# PWM_BoardSchem.net
KiCad netlist of a schematic drawn in Altium Designer
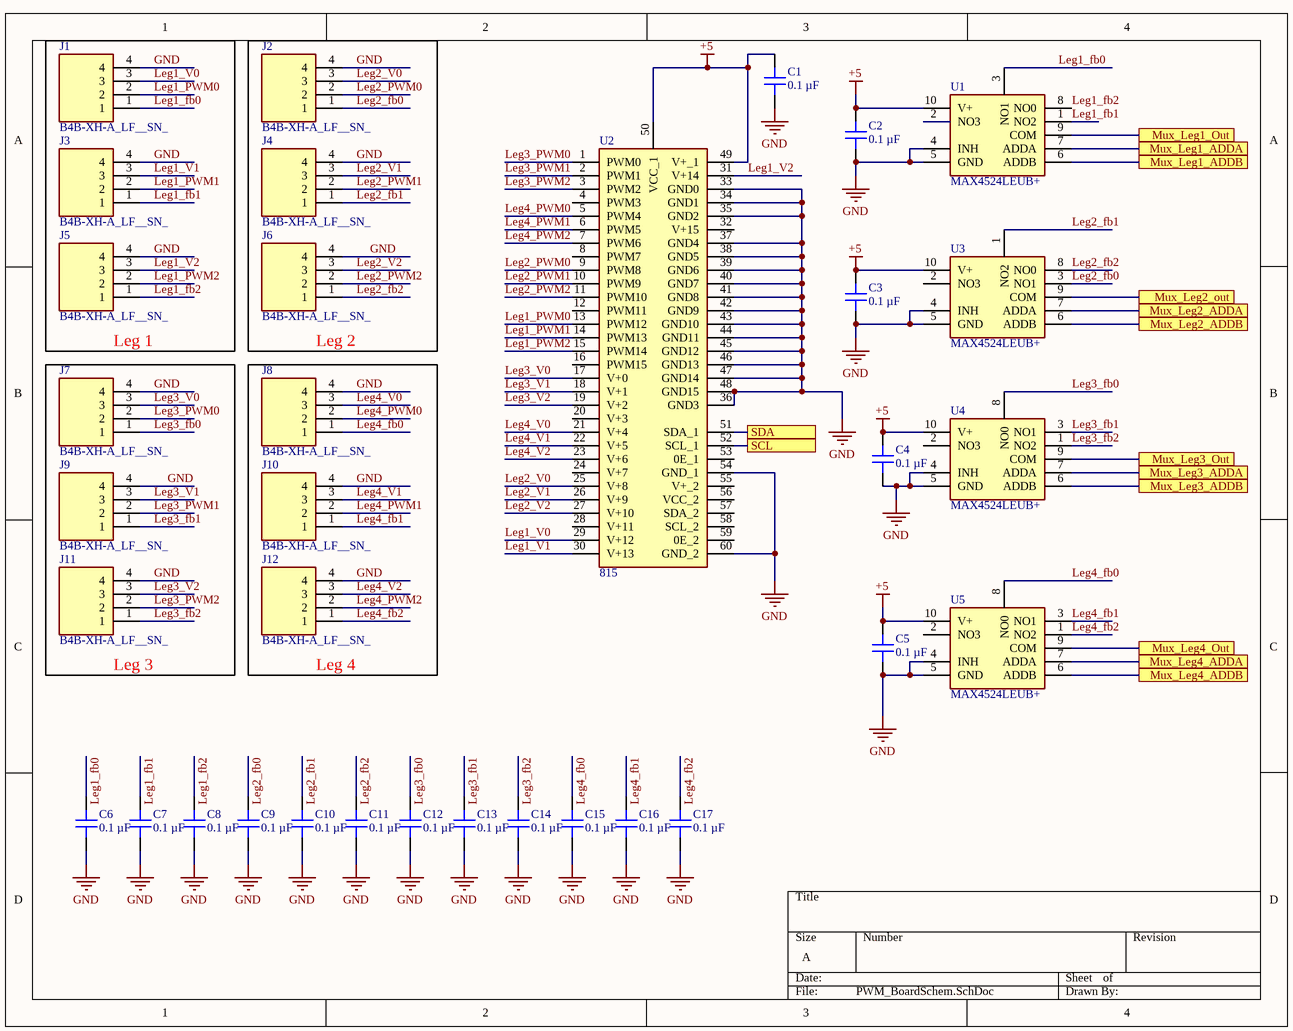
[diagram p0: PWM_BoardSchem.SchDoc]

(export (version "E")
  (design (tool "Eeschema 10.0.6"))
  (components
    (comp (ref "C1")
      (value "0.1 µF")
      (footprint "CAP 1210_3225 - 1MM")
      (description "CAP CER 0.1UF 50V C0G/NP0 1210")
      (fields (field (name "PART NUMBER") "C1210C104J5GACAUTO") (field (name "MANUFACTURER") "KEMET"))
      (libsource (lib "Celestial Altium Library - altium_library") (part "Capacitor"))
    )
    (comp (ref "C2")
      (value "0.1 µF")
      (footprint "CAP 1210_3225 - 1MM")
      (description "CAP CER 0.1UF 50V C0G/NP0 1210")
      (fields (field (name "PART NUMBER") "C1210C104J5GACAUTO") (field (name "MANUFACTURER") "KEMET"))
      (libsource (lib "Celestial Altium Library - altium_library") (part "Capacitor"))
    )
    (comp (ref "C3")
      (value "0.1 µF")
      (footprint "CAP 1210_3225 - 1MM")
      (description "CAP CER 0.1UF 50V C0G/NP0 1210")
      (fields (field (name "PART NUMBER") "C1210C104J5GACAUTO") (field (name "MANUFACTURER") "KEMET"))
      (libsource (lib "Celestial Altium Library - altium_library") (part "Capacitor"))
    )
    (comp (ref "C4")
      (value "0.1 µF")
      (footprint "CAP 1210_3225 - 1MM")
      (description "CAP CER 0.1UF 50V C0G/NP0 1210")
      (fields (field (name "PART NUMBER") "C1210C104J5GACAUTO") (field (name "MANUFACTURER") "KEMET"))
      (libsource (lib "Celestial Altium Library - altium_library") (part "Capacitor"))
    )
    (comp (ref "C5")
      (value "0.1 µF")
      (footprint "CAP 1210_3225 - 1MM")
      (description "CAP CER 0.1UF 50V C0G/NP0 1210")
      (fields (field (name "PART NUMBER") "C1210C104J5GACAUTO") (field (name "MANUFACTURER") "KEMET"))
      (libsource (lib "Celestial Altium Library - altium_library") (part "Capacitor"))
    )
    (comp (ref "C6")
      (value "0.1 µF")
      (footprint "CAP 1210_3225 - 1MM")
      (description "CAP CER 0.1UF 50V C0G/NP0 1210")
      (fields (field (name "PART NUMBER") "C1210C104J5GACAUTO") (field (name "MANUFACTURER") "KEMET"))
      (libsource (lib "Celestial Altium Library - altium_library") (part "Capacitor"))
    )
    (comp (ref "C7")
      (value "0.1 µF")
      (footprint "CAP 1210_3225 - 1MM")
      (description "CAP CER 0.1UF 50V C0G/NP0 1210")
      (fields (field (name "PART NUMBER") "C1210C104J5GACAUTO") (field (name "MANUFACTURER") "KEMET"))
      (libsource (lib "Celestial Altium Library - altium_library") (part "Capacitor"))
    )
    (comp (ref "C8")
      (value "0.1 µF")
      (footprint "CAP 1210_3225 - 1MM")
      (description "CAP CER 0.1UF 50V C0G/NP0 1210")
      (fields (field (name "PART NUMBER") "C1210C104J5GACAUTO") (field (name "MANUFACTURER") "KEMET"))
      (libsource (lib "Celestial Altium Library - altium_library") (part "Capacitor"))
    )
    (comp (ref "C9")
      (value "0.1 µF")
      (footprint "CAP 1210_3225 - 1MM")
      (description "CAP CER 0.1UF 50V C0G/NP0 1210")
      (fields (field (name "PART NUMBER") "C1210C104J5GACAUTO") (field (name "MANUFACTURER") "KEMET"))
      (libsource (lib "Celestial Altium Library - altium_library") (part "Capacitor"))
    )
    (comp (ref "C10")
      (value "0.1 µF")
      (footprint "CAP 1210_3225 - 1MM")
      (description "CAP CER 0.1UF 50V C0G/NP0 1210")
      (fields (field (name "PART NUMBER") "C1210C104J5GACAUTO") (field (name "MANUFACTURER") "KEMET"))
      (libsource (lib "Celestial Altium Library - altium_library") (part "Capacitor"))
    )
    (comp (ref "C11")
      (value "0.1 µF")
      (footprint "CAP 1210_3225 - 1MM")
      (description "CAP CER 0.1UF 50V C0G/NP0 1210")
      (fields (field (name "PART NUMBER") "C1210C104J5GACAUTO") (field (name "MANUFACTURER") "KEMET"))
      (libsource (lib "Celestial Altium Library - altium_library") (part "Capacitor"))
    )
    (comp (ref "C12")
      (value "0.1 µF")
      (footprint "CAP 1210_3225 - 1MM")
      (description "CAP CER 0.1UF 50V C0G/NP0 1210")
      (fields (field (name "PART NUMBER") "C1210C104J5GACAUTO") (field (name "MANUFACTURER") "KEMET"))
      (libsource (lib "Celestial Altium Library - altium_library") (part "Capacitor"))
    )
    (comp (ref "C13")
      (value "0.1 µF")
      (footprint "CAP 1210_3225 - 1MM")
      (description "CAP CER 0.1UF 50V C0G/NP0 1210")
      (fields (field (name "PART NUMBER") "C1210C104J5GACAUTO") (field (name "MANUFACTURER") "KEMET"))
      (libsource (lib "Celestial Altium Library - altium_library") (part "Capacitor"))
    )
    (comp (ref "C14")
      (value "0.1 µF")
      (footprint "CAP 1210_3225 - 1MM")
      (description "CAP CER 0.1UF 50V C0G/NP0 1210")
      (fields (field (name "PART NUMBER") "C1210C104J5GACAUTO") (field (name "MANUFACTURER") "KEMET"))
      (libsource (lib "Celestial Altium Library - altium_library") (part "Capacitor"))
    )
    (comp (ref "C15")
      (value "0.1 µF")
      (footprint "CAP 1210_3225 - 1MM")
      (description "CAP CER 0.1UF 50V C0G/NP0 1210")
      (fields (field (name "PART NUMBER") "C1210C104J5GACAUTO") (field (name "MANUFACTURER") "KEMET"))
      (libsource (lib "Celestial Altium Library - altium_library") (part "Capacitor"))
    )
    (comp (ref "C16")
      (value "0.1 µF")
      (footprint "CAP 1210_3225 - 1MM")
      (description "CAP CER 0.1UF 50V C0G/NP0 1210")
      (fields (field (name "PART NUMBER") "C1210C104J5GACAUTO") (field (name "MANUFACTURER") "KEMET"))
      (libsource (lib "Celestial Altium Library - altium_library") (part "Capacitor"))
    )
    (comp (ref "C17")
      (value "0.1 µF")
      (footprint "CAP 1210_3225 - 1MM")
      (description "CAP CER 0.1UF 50V C0G/NP0 1210")
      (fields (field (name "PART NUMBER") "C1210C104J5GACAUTO") (field (name "MANUFACTURER") "KEMET"))
      (libsource (lib "Celestial Altium Library - altium_library") (part "Capacitor"))
    )
    (comp (ref "J1")
      (value "B4B-XH-A_LF__SN_")
      (footprint "SamacSys:B4BXHALFSN")
      (description "Connector")
      (fields (field (name "MANUFACTURER_PART_NUMBER") "B4B-XH-A(LF)(SN)"))
      (libsource (lib "*") (part "B4B-XH-A_LF__SN_"))
    )
    (comp (ref "J2")
      (value "B4B-XH-A_LF__SN_")
      (footprint "SamacSys:B4BXHALFSN")
      (description "Connector")
      (fields (field (name "MANUFACTURER_PART_NUMBER") "B4B-XH-A(LF)(SN)"))
      (libsource (lib "*") (part "B4B-XH-A_LF__SN_"))
    )
    (comp (ref "J3")
      (value "B4B-XH-A_LF__SN_")
      (footprint "SamacSys:B4BXHALFSN")
      (description "Connector")
      (fields (field (name "MANUFACTURER_PART_NUMBER") "B4B-XH-A(LF)(SN)"))
      (libsource (lib "*") (part "B4B-XH-A_LF__SN_"))
    )
    (comp (ref "J4")
      (value "B4B-XH-A_LF__SN_")
      (footprint "SamacSys:B4BXHALFSN")
      (description "Connector")
      (fields (field (name "MANUFACTURER_PART_NUMBER") "B4B-XH-A(LF)(SN)"))
      (libsource (lib "*") (part "B4B-XH-A_LF__SN_"))
    )
    (comp (ref "J5")
      (value "B4B-XH-A_LF__SN_")
      (footprint "SamacSys:B4BXHALFSN")
      (description "Connector")
      (fields (field (name "MANUFACTURER_PART_NUMBER") "B4B-XH-A(LF)(SN)"))
      (libsource (lib "*") (part "B4B-XH-A_LF__SN_"))
    )
    (comp (ref "J6")
      (value "B4B-XH-A_LF__SN_")
      (footprint "SamacSys:B4BXHALFSN")
      (description "Connector")
      (fields (field (name "MANUFACTURER_PART_NUMBER") "B4B-XH-A(LF)(SN)"))
      (libsource (lib "*") (part "B4B-XH-A_LF__SN_"))
    )
    (comp (ref "J7")
      (value "B4B-XH-A_LF__SN_")
      (footprint "SamacSys:B4BXHALFSN")
      (description "Connector")
      (fields (field (name "MANUFACTURER_PART_NUMBER") "B4B-XH-A(LF)(SN)"))
      (libsource (lib "*") (part "B4B-XH-A_LF__SN_"))
    )
    (comp (ref "J8")
      (value "B4B-XH-A_LF__SN_")
      (footprint "SamacSys:B4BXHALFSN")
      (description "Connector")
      (fields (field (name "MANUFACTURER_PART_NUMBER") "B4B-XH-A(LF)(SN)"))
      (libsource (lib "*") (part "B4B-XH-A_LF__SN_"))
    )
    (comp (ref "J9")
      (value "B4B-XH-A_LF__SN_")
      (footprint "SamacSys:B4BXHALFSN")
      (description "Connector")
      (fields (field (name "MANUFACTURER_PART_NUMBER") "B4B-XH-A(LF)(SN)"))
      (libsource (lib "*") (part "B4B-XH-A_LF__SN_"))
    )
    (comp (ref "J10")
      (value "B4B-XH-A_LF__SN_")
      (footprint "SamacSys:B4BXHALFSN")
      (description "Connector")
      (fields (field (name "MANUFACTURER_PART_NUMBER") "B4B-XH-A(LF)(SN)"))
      (libsource (lib "*") (part "B4B-XH-A_LF__SN_"))
    )
    (comp (ref "J11")
      (value "B4B-XH-A_LF__SN_")
      (footprint "SamacSys:B4BXHALFSN")
      (description "Connector")
      (fields (field (name "MANUFACTURER_PART_NUMBER") "B4B-XH-A(LF)(SN)"))
      (libsource (lib "*") (part "B4B-XH-A_LF__SN_"))
    )
    (comp (ref "J12")
      (value "B4B-XH-A_LF__SN_")
      (footprint "SamacSys:B4BXHALFSN")
      (description "Connector")
      (fields (field (name "MANUFACTURER_PART_NUMBER") "B4B-XH-A(LF)(SN)"))
      (libsource (lib "*") (part "B4B-XH-A_LF__SN_"))
    )
    (comp (ref "U1")
      (value "MAX4524LEUB+")
      (footprint "SamacSys:SOP50P490X110-10N")
      (description "Integrated Circuit")
      (fields (field (name "MOUSER PART NUMBER") "700-MAX4524LEUB+"))
      (libsource (lib "") (part "MAX4524LEUB+_1"))
    )
    (comp (ref "U2")
      (value "815")
      (footprint "SamacSys:815")
      (description "Undefined or Miscellaneous")
      (fields (field (name "MOUSER PART NUMBER") "485-815"))
      (libsource (lib "*") (part "815"))
    )
    (comp (ref "U3")
      (value "MAX4524LEUB+")
      (footprint "SamacSys:SOP50P490X110-10N")
      (description "Integrated Circuit")
      (fields (field (name "MOUSER PART NUMBER") "700-MAX4524LEUB+"))
      (libsource (lib "") (part "MAX4524LEUB+_2"))
    )
    (comp (ref "U4")
      (value "MAX4524LEUB+")
      (footprint "SamacSys:SOP50P490X110-10N")
      (description "Integrated Circuit")
      (fields (field (name "MOUSER PART NUMBER") "700-MAX4524LEUB+"))
      (libsource (lib "*") (part "MAX4524LEUB+"))
    )
    (comp (ref "U5")
      (value "MAX4524LEUB+")
      (footprint "SamacSys:SOP50P490X110-10N")
      (description "Integrated Circuit")
      (fields (field (name "MOUSER PART NUMBER") "700-MAX4524LEUB+"))
      (libsource (lib "*") (part "MAX4524LEUB+"))
    )
  )
  (nets
    (net (code "1") (name "+5") (class "Default")
      (node (ref "C1") (pin "2") (pinfunction "2_2") (pintype "passive"))
      (node (ref "C2") (pin "2") (pinfunction "2_2") (pintype "passive"))
      (node (ref "C3") (pin "2") (pinfunction "2_2") (pintype "passive"))
      (node (ref "C4") (pin "2") (pinfunction "2_2") (pintype "passive"))
      (node (ref "C5") (pin "2") (pinfunction "2_2") (pintype "passive"))
      (node (ref "U1") (pin "10") (pinfunction "V+_10") (pintype "passive"))
      (node (ref "U2") (pin "49") (pinfunction "V+_1_49") (pintype "passive"))
      (node (ref "U2") (pin "50") (pinfunction "VCC_1_50") (pintype "passive"))
      (node (ref "U3") (pin "10") (pinfunction "V+_10") (pintype "passive"))
      (node (ref "U4") (pin "10") (pinfunction "V+_10") (pintype "passive"))
      (node (ref "U5") (pin "10") (pinfunction "V+_10") (pintype "passive"))
    )
    (net (code "3") (name "/Leg1_PWM0") (class "Default")
      (node (ref "J1") (pin "2") (pinfunction "2_2") (pintype "passive"))
      (node (ref "U2") (pin "13") (pinfunction "PWM12_13") (pintype "passive"))
    )
    (net (code "4") (name "/Leg1_PWM1") (class "Default")
      (node (ref "J3") (pin "2") (pinfunction "2_2") (pintype "passive"))
      (node (ref "U2") (pin "14") (pinfunction "PWM13_14") (pintype "passive"))
    )
    (net (code "5") (name "/Leg1_PWM2") (class "Default")
      (node (ref "J5") (pin "2") (pinfunction "2_2") (pintype "passive"))
      (node (ref "U2") (pin "15") (pinfunction "PWM14_15") (pintype "passive"))
    )
    (net (code "6") (name "/Leg1_V0") (class "Default")
      (node (ref "J1") (pin "3") (pinfunction "3_3") (pintype "passive"))
      (node (ref "U2") (pin "29") (pinfunction "V+12_29") (pintype "passive"))
    )
    (net (code "7") (name "/Leg1_V1") (class "Default")
      (node (ref "J3") (pin "3") (pinfunction "3_3") (pintype "passive"))
      (node (ref "U2") (pin "30") (pinfunction "V+13_30") (pintype "passive"))
    )
    (net (code "8") (name "/Leg1_V2") (class "Default")
      (node (ref "J5") (pin "3") (pinfunction "3_3") (pintype "passive"))
      (node (ref "U2") (pin "31") (pinfunction "V+14_31") (pintype "passive"))
    )
    (net (code "9") (name "/Leg1_fb0") (class "Default")
      (node (ref "C6") (pin "2") (pinfunction "2_2") (pintype "passive"))
      (node (ref "J1") (pin "1") (pinfunction "1_1") (pintype "passive"))
      (node (ref "U1") (pin "3") (pinfunction "NO1_3") (pintype "passive"))
    )
    (net (code "10") (name "/Leg1_fb1") (class "Default")
      (node (ref "C7") (pin "2") (pinfunction "2_2") (pintype "passive"))
      (node (ref "J3") (pin "1") (pinfunction "1_1") (pintype "passive"))
      (node (ref "U1") (pin "1") (pinfunction "NO2_1") (pintype "passive"))
    )
    (net (code "11") (name "/Leg1_fb2") (class "Default")
      (node (ref "C8") (pin "2") (pinfunction "2_2") (pintype "passive"))
      (node (ref "J5") (pin "1") (pinfunction "1_1") (pintype "passive"))
      (node (ref "U1") (pin "8") (pinfunction "NO0_8") (pintype "passive"))
    )
    (net (code "12") (name "/Leg2_PWM0") (class "Default")
      (node (ref "J2") (pin "2") (pinfunction "2_2") (pintype "passive"))
      (node (ref "U2") (pin "9") (pinfunction "PWM8_9") (pintype "passive"))
    )
    (net (code "13") (name "/Leg2_PWM1") (class "Default")
      (node (ref "J4") (pin "2") (pinfunction "2_2") (pintype "passive"))
      (node (ref "U2") (pin "10") (pinfunction "PWM9_10") (pintype "passive"))
    )
    (net (code "14") (name "/Leg2_PWM2") (class "Default")
      (node (ref "J6") (pin "2") (pinfunction "2_2") (pintype "passive"))
      (node (ref "U2") (pin "11") (pinfunction "PWM10_11") (pintype "passive"))
    )
    (net (code "15") (name "/Leg2_V0") (class "Default")
      (node (ref "J2") (pin "3") (pinfunction "3_3") (pintype "passive"))
      (node (ref "U2") (pin "25") (pinfunction "V+8_25") (pintype "passive"))
    )
    (net (code "16") (name "/Leg2_V1") (class "Default")
      (node (ref "J4") (pin "3") (pinfunction "3_3") (pintype "passive"))
      (node (ref "U2") (pin "26") (pinfunction "V+9_26") (pintype "passive"))
    )
    (net (code "17") (name "/Leg2_V2") (class "Default")
      (node (ref "J6") (pin "3") (pinfunction "3_3") (pintype "passive"))
      (node (ref "U2") (pin "27") (pinfunction "V+10_27") (pintype "passive"))
    )
    (net (code "18") (name "/Leg2_fb0") (class "Default")
      (node (ref "C9") (pin "2") (pinfunction "2_2") (pintype "passive"))
      (node (ref "J2") (pin "1") (pinfunction "1_1") (pintype "passive"))
      (node (ref "U3") (pin "3") (pinfunction "NO1_3") (pintype "passive"))
    )
    (net (code "19") (name "/Leg2_fb1") (class "Default")
      (node (ref "C10") (pin "2") (pinfunction "2_2") (pintype "passive"))
      (node (ref "J4") (pin "1") (pinfunction "1_1") (pintype "passive"))
      (node (ref "U3") (pin "1") (pinfunction "NO2_1") (pintype "passive"))
    )
    (net (code "20") (name "/Leg2_fb2") (class "Default")
      (node (ref "C11") (pin "2") (pinfunction "2_2") (pintype "passive"))
      (node (ref "J6") (pin "1") (pinfunction "1_1") (pintype "passive"))
      (node (ref "U3") (pin "8") (pinfunction "NO0_8") (pintype "passive"))
    )
    (net (code "21") (name "/Leg3_PWM0") (class "Default")
      (node (ref "J7") (pin "2") (pinfunction "2_2") (pintype "passive"))
      (node (ref "U2") (pin "1") (pinfunction "PWM0_1") (pintype "passive"))
    )
    (net (code "22") (name "/Leg3_PWM1") (class "Default")
      (node (ref "J9") (pin "2") (pinfunction "2_2") (pintype "passive"))
      (node (ref "U2") (pin "2") (pinfunction "PWM1_2") (pintype "passive"))
    )
    (net (code "23") (name "/Leg3_PWM2") (class "Default")
      (node (ref "J11") (pin "2") (pinfunction "2_2") (pintype "passive"))
      (node (ref "U2") (pin "3") (pinfunction "PWM2_3") (pintype "passive"))
    )
    (net (code "24") (name "/Leg3_V0") (class "Default")
      (node (ref "J7") (pin "3") (pinfunction "3_3") (pintype "passive"))
      (node (ref "U2") (pin "17") (pinfunction "V+0_17") (pintype "passive"))
    )
    (net (code "25") (name "/Leg3_V1") (class "Default")
      (node (ref "J9") (pin "3") (pinfunction "3_3") (pintype "passive"))
      (node (ref "U2") (pin "18") (pinfunction "V+1_18") (pintype "passive"))
    )
    (net (code "26") (name "/Leg3_V2") (class "Default")
      (node (ref "J11") (pin "3") (pinfunction "3_3") (pintype "passive"))
      (node (ref "U2") (pin "19") (pinfunction "V+2_19") (pintype "passive"))
    )
    (net (code "27") (name "/Leg3_fb0") (class "Default")
      (node (ref "C12") (pin "2") (pinfunction "2_2") (pintype "passive"))
      (node (ref "J7") (pin "1") (pinfunction "1_1") (pintype "passive"))
      (node (ref "U4") (pin "8") (pinfunction "NO0_8") (pintype "passive"))
    )
    (net (code "28") (name "/Leg3_fb1") (class "Default")
      (node (ref "C13") (pin "2") (pinfunction "2_2") (pintype "passive"))
      (node (ref "J9") (pin "1") (pinfunction "1_1") (pintype "passive"))
      (node (ref "U4") (pin "3") (pinfunction "NO1_3") (pintype "passive"))
    )
    (net (code "29") (name "/Leg3_fb2") (class "Default")
      (node (ref "C14") (pin "2") (pinfunction "2_2") (pintype "passive"))
      (node (ref "J11") (pin "1") (pinfunction "1_1") (pintype "passive"))
      (node (ref "U4") (pin "1") (pinfunction "NO2_1") (pintype "passive"))
    )
    (net (code "30") (name "/Leg4_PWM0") (class "Default")
      (node (ref "J8") (pin "2") (pinfunction "2_2") (pintype "passive"))
      (node (ref "U2") (pin "5") (pinfunction "PWM4_5") (pintype "passive"))
    )
    (net (code "31") (name "/Leg4_PWM1") (class "Default")
      (node (ref "J10") (pin "2") (pinfunction "2_2") (pintype "passive"))
      (node (ref "U2") (pin "6") (pinfunction "PWM5_6") (pintype "passive"))
    )
    (net (code "32") (name "/Leg4_PWM2") (class "Default")
      (node (ref "J12") (pin "2") (pinfunction "2_2") (pintype "passive"))
      (node (ref "U2") (pin "7") (pinfunction "PWM6_7") (pintype "passive"))
    )
    (net (code "33") (name "/Leg4_V0") (class "Default")
      (node (ref "J8") (pin "3") (pinfunction "3_3") (pintype "passive"))
      (node (ref "U2") (pin "21") (pinfunction "V+4_21") (pintype "passive"))
    )
    (net (code "34") (name "/Leg4_V1") (class "Default")
      (node (ref "J10") (pin "3") (pinfunction "3_3") (pintype "passive"))
      (node (ref "U2") (pin "22") (pinfunction "V+5_22") (pintype "passive"))
    )
    (net (code "35") (name "/Leg4_V2") (class "Default")
      (node (ref "J12") (pin "3") (pinfunction "3_3") (pintype "passive"))
      (node (ref "U2") (pin "23") (pinfunction "V+6_23") (pintype "passive"))
    )
    (net (code "36") (name "/Leg4_fb0") (class "Default")
      (node (ref "C15") (pin "2") (pinfunction "2_2") (pintype "passive"))
      (node (ref "J8") (pin "1") (pinfunction "1_1") (pintype "passive"))
      (node (ref "U5") (pin "8") (pinfunction "NO0_8") (pintype "passive"))
    )
    (net (code "37") (name "/Leg4_fb1") (class "Default")
      (node (ref "C16") (pin "2") (pinfunction "2_2") (pintype "passive"))
      (node (ref "J10") (pin "1") (pinfunction "1_1") (pintype "passive"))
      (node (ref "U5") (pin "3") (pinfunction "NO1_3") (pintype "passive"))
    )
    (net (code "38") (name "/Leg4_fb2") (class "Default")
      (node (ref "C17") (pin "2") (pinfunction "2_2") (pintype "passive"))
      (node (ref "J12") (pin "1") (pinfunction "1_1") (pintype "passive"))
      (node (ref "U5") (pin "1") (pinfunction "NO2_1") (pintype "passive"))
    )
    (net (code "39") (name "/Mux_Leg1_ADDA") (class "Default")
      (node (ref "U1") (pin "7") (pinfunction "ADDA_7") (pintype "passive"))
    )
    (net (code "40") (name "/Mux_Leg1_ADDB") (class "Default")
      (node (ref "U1") (pin "6") (pinfunction "ADDB_6") (pintype "passive"))
    )
    (net (code "41") (name "/Mux_Leg1_Out") (class "Default")
      (node (ref "U1") (pin "9") (pinfunction "COM_9") (pintype "passive"))
    )
    (net (code "42") (name "/Mux_Leg2_ADDA") (class "Default")
      (node (ref "U3") (pin "7") (pinfunction "ADDA_7") (pintype "passive"))
    )
    (net (code "43") (name "/Mux_Leg2_ADDB") (class "Default")
      (node (ref "U3") (pin "6") (pinfunction "ADDB_6") (pintype "passive"))
    )
    (net (code "44") (name "/Mux_Leg2_out") (class "Default")
      (node (ref "U3") (pin "9") (pinfunction "COM_9") (pintype "passive"))
    )
    (net (code "45") (name "/Mux_Leg3_ADDA") (class "Default")
      (node (ref "U4") (pin "7") (pinfunction "ADDA_7") (pintype "passive"))
    )
    (net (code "46") (name "/Mux_Leg3_ADDB") (class "Default")
      (node (ref "U4") (pin "6") (pinfunction "ADDB_6") (pintype "passive"))
    )
    (net (code "47") (name "/Mux_Leg3_Out") (class "Default")
      (node (ref "U4") (pin "9") (pinfunction "COM_9") (pintype "passive"))
    )
    (net (code "48") (name "/Mux_Leg4_ADDA") (class "Default")
      (node (ref "U5") (pin "7") (pinfunction "ADDA_7") (pintype "passive"))
    )
    (net (code "49") (name "/Mux_Leg4_ADDB") (class "Default")
      (node (ref "U5") (pin "6") (pinfunction "ADDB_6") (pintype "passive"))
    )
    (net (code "50") (name "/Mux_Leg4_Out") (class "Default")
      (node (ref "U5") (pin "9") (pinfunction "COM_9") (pintype "passive"))
    )
    (net (code "51") (name "/SCL") (class "Default")
      (node (ref "U2") (pin "52") (pinfunction "SCL_1_52") (pintype "passive"))
    )
    (net (code "52") (name "/SDA") (class "Default")
      (node (ref "U2") (pin "51") (pinfunction "SDA_1_51") (pintype "passive"))
    )
    (net (code "53") (name "GND") (class "Default")
      (node (ref "C1") (pin "1") (pinfunction "1_1") (pintype "passive"))
      (node (ref "C10") (pin "1") (pinfunction "1_1") (pintype "passive"))
      (node (ref "C11") (pin "1") (pinfunction "1_1") (pintype "passive"))
      (node (ref "C12") (pin "1") (pinfunction "1_1") (pintype "passive"))
      (node (ref "C13") (pin "1") (pinfunction "1_1") (pintype "passive"))
      (node (ref "C14") (pin "1") (pinfunction "1_1") (pintype "passive"))
      (node (ref "C15") (pin "1") (pinfunction "1_1") (pintype "passive"))
      (node (ref "C16") (pin "1") (pinfunction "1_1") (pintype "passive"))
      (node (ref "C17") (pin "1") (pinfunction "1_1") (pintype "passive"))
      (node (ref "C2") (pin "1") (pinfunction "1_1") (pintype "passive"))
      (node (ref "C3") (pin "1") (pinfunction "1_1") (pintype "passive"))
      (node (ref "C4") (pin "1") (pinfunction "1_1") (pintype "passive"))
      (node (ref "C5") (pin "1") (pinfunction "1_1") (pintype "passive"))
      (node (ref "C6") (pin "1") (pinfunction "1_1") (pintype "passive"))
      (node (ref "C7") (pin "1") (pinfunction "1_1") (pintype "passive"))
      (node (ref "C8") (pin "1") (pinfunction "1_1") (pintype "passive"))
      (node (ref "C9") (pin "1") (pinfunction "1_1") (pintype "passive"))
      (node (ref "J1") (pin "4") (pinfunction "4_4") (pintype "passive"))
      (node (ref "J10") (pin "4") (pinfunction "4_4") (pintype "passive"))
      (node (ref "J11") (pin "4") (pinfunction "4_4") (pintype "passive"))
      (node (ref "J12") (pin "4") (pinfunction "4_4") (pintype "passive"))
      (node (ref "J2") (pin "4") (pinfunction "4_4") (pintype "passive"))
      (node (ref "J3") (pin "4") (pinfunction "4_4") (pintype "passive"))
      (node (ref "J4") (pin "4") (pinfunction "4_4") (pintype "passive"))
      (node (ref "J5") (pin "4") (pinfunction "4_4") (pintype "passive"))
      (node (ref "J6") (pin "4") (pinfunction "4_4") (pintype "passive"))
      (node (ref "J7") (pin "4") (pinfunction "4_4") (pintype "passive"))
      (node (ref "J8") (pin "4") (pinfunction "4_4") (pintype "passive"))
      (node (ref "J9") (pin "4") (pinfunction "4_4") (pintype "passive"))
      (node (ref "U1") (pin "4") (pinfunction "INH_4") (pintype "passive"))
      (node (ref "U1") (pin "5") (pinfunction "GND_5") (pintype "passive"))
      (node (ref "U2") (pin "33") (pinfunction "GND0_33") (pintype "passive"))
      (node (ref "U2") (pin "34") (pinfunction "GND1_34") (pintype "passive"))
      (node (ref "U2") (pin "35") (pinfunction "GND2_35") (pintype "passive"))
      (node (ref "U2") (pin "36") (pinfunction "GND3_36") (pintype "passive"))
      (node (ref "U2") (pin "37") (pinfunction "GND4_37") (pintype "passive"))
      (node (ref "U2") (pin "38") (pinfunction "GND5_38") (pintype "passive"))
      (node (ref "U2") (pin "39") (pinfunction "GND6_39") (pintype "passive"))
      (node (ref "U2") (pin "40") (pinfunction "GND7_40") (pintype "passive"))
      (node (ref "U2") (pin "41") (pinfunction "GND8_41") (pintype "passive"))
      (node (ref "U2") (pin "42") (pinfunction "GND9_42") (pintype "passive"))
      (node (ref "U2") (pin "43") (pinfunction "GND10_43") (pintype "passive"))
      (node (ref "U2") (pin "44") (pinfunction "GND11_44") (pintype "passive"))
      (node (ref "U2") (pin "45") (pinfunction "GND12_45") (pintype "passive"))
      (node (ref "U2") (pin "46") (pinfunction "GND13_46") (pintype "passive"))
      (node (ref "U2") (pin "47") (pinfunction "GND14_47") (pintype "passive"))
      (node (ref "U2") (pin "48") (pinfunction "GND15_48") (pintype "passive"))
      (node (ref "U2") (pin "54") (pinfunction "GND_1_54") (pintype "passive"))
      (node (ref "U2") (pin "60") (pinfunction "GND_2_60") (pintype "passive"))
      (node (ref "U3") (pin "4") (pinfunction "INH_4") (pintype "passive"))
      (node (ref "U3") (pin "5") (pinfunction "GND_5") (pintype "passive"))
      (node (ref "U4") (pin "4") (pinfunction "INH_4") (pintype "passive"))
      (node (ref "U4") (pin "5") (pinfunction "GND_5") (pintype "passive"))
      (node (ref "U5") (pin "4") (pinfunction "INH_4") (pintype "passive"))
      (node (ref "U5") (pin "5") (pinfunction "GND_5") (pintype "passive"))
    )
    (net (code "54") (name "unconnected-(U1-NO3-Pad2)") (class "Default")
      (node (ref "U1") (pin "2") (pinfunction "NO3_2") (pintype "passive"))
    )
    (net (code "55") (name "unconnected-(U2-0E_1-Pad53)") (class "Default")
      (node (ref "U2") (pin "53") (pinfunction "0E_1_53") (pintype "passive"))
    )
    (net (code "56") (name "unconnected-(U2-0E_2-Pad59)") (class "Default")
      (node (ref "U2") (pin "59") (pinfunction "0E_2_59") (pintype "passive"))
    )
    (net (code "57") (name "unconnected-(U2-PWM3-Pad4)") (class "Default")
      (node (ref "U2") (pin "4") (pinfunction "PWM3_4") (pintype "passive"))
    )
    (net (code "58") (name "unconnected-(U2-PWM7-Pad8)") (class "Default")
      (node (ref "U2") (pin "8") (pinfunction "PWM7_8") (pintype "passive"))
    )
    (net (code "59") (name "unconnected-(U2-PWM11-Pad12)") (class "Default")
      (node (ref "U2") (pin "12") (pinfunction "PWM11_12") (pintype "passive"))
    )
    (net (code "60") (name "unconnected-(U2-PWM15-Pad16)") (class "Default")
      (node (ref "U2") (pin "16") (pinfunction "PWM15_16") (pintype "passive"))
    )
    (net (code "61") (name "unconnected-(U2-SCL_2-Pad58)") (class "Default")
      (node (ref "U2") (pin "58") (pinfunction "SCL_2_58") (pintype "passive"))
    )
    (net (code "62") (name "unconnected-(U2-SDA_2-Pad57)") (class "Default")
      (node (ref "U2") (pin "57") (pinfunction "SDA_2_57") (pintype "passive"))
    )
    (net (code "63") (name "unconnected-(U2-V+3-Pad20)") (class "Default")
      (node (ref "U2") (pin "20") (pinfunction "V+3_20") (pintype "passive"))
    )
    (net (code "64") (name "unconnected-(U2-V+7-Pad24)") (class "Default")
      (node (ref "U2") (pin "24") (pinfunction "V+7_24") (pintype "passive"))
    )
    (net (code "65") (name "unconnected-(U2-V+11-Pad28)") (class "Default")
      (node (ref "U2") (pin "28") (pinfunction "V+11_28") (pintype "passive"))
    )
    (net (code "66") (name "unconnected-(U2-V+15-Pad32)") (class "Default")
      (node (ref "U2") (pin "32") (pinfunction "V+15_32") (pintype "passive"))
    )
    (net (code "67") (name "unconnected-(U2-V+_2-Pad55)") (class "Default")
      (node (ref "U2") (pin "55") (pinfunction "V+_2_55") (pintype "passive"))
    )
    (net (code "68") (name "unconnected-(U2-VCC_2-Pad56)") (class "Default")
      (node (ref "U2") (pin "56") (pinfunction "VCC_2_56") (pintype "passive"))
    )
    (net (code "69") (name "unconnected-(U3-NO3-Pad2)") (class "Default")
      (node (ref "U3") (pin "2") (pinfunction "NO3_2") (pintype "passive"))
    )
    (net (code "70") (name "unconnected-(U4-NO3-Pad2)") (class "Default")
      (node (ref "U4") (pin "2") (pinfunction "NO3_2") (pintype "passive"))
    )
    (net (code "71") (name "unconnected-(U5-NO3-Pad2)") (class "Default")
      (node (ref "U5") (pin "2") (pinfunction "NO3_2") (pintype "passive"))
    )
  )
)
